# JHDH-8412_1247.net
KiCad netlist of a schematic drawn in Altium Designer
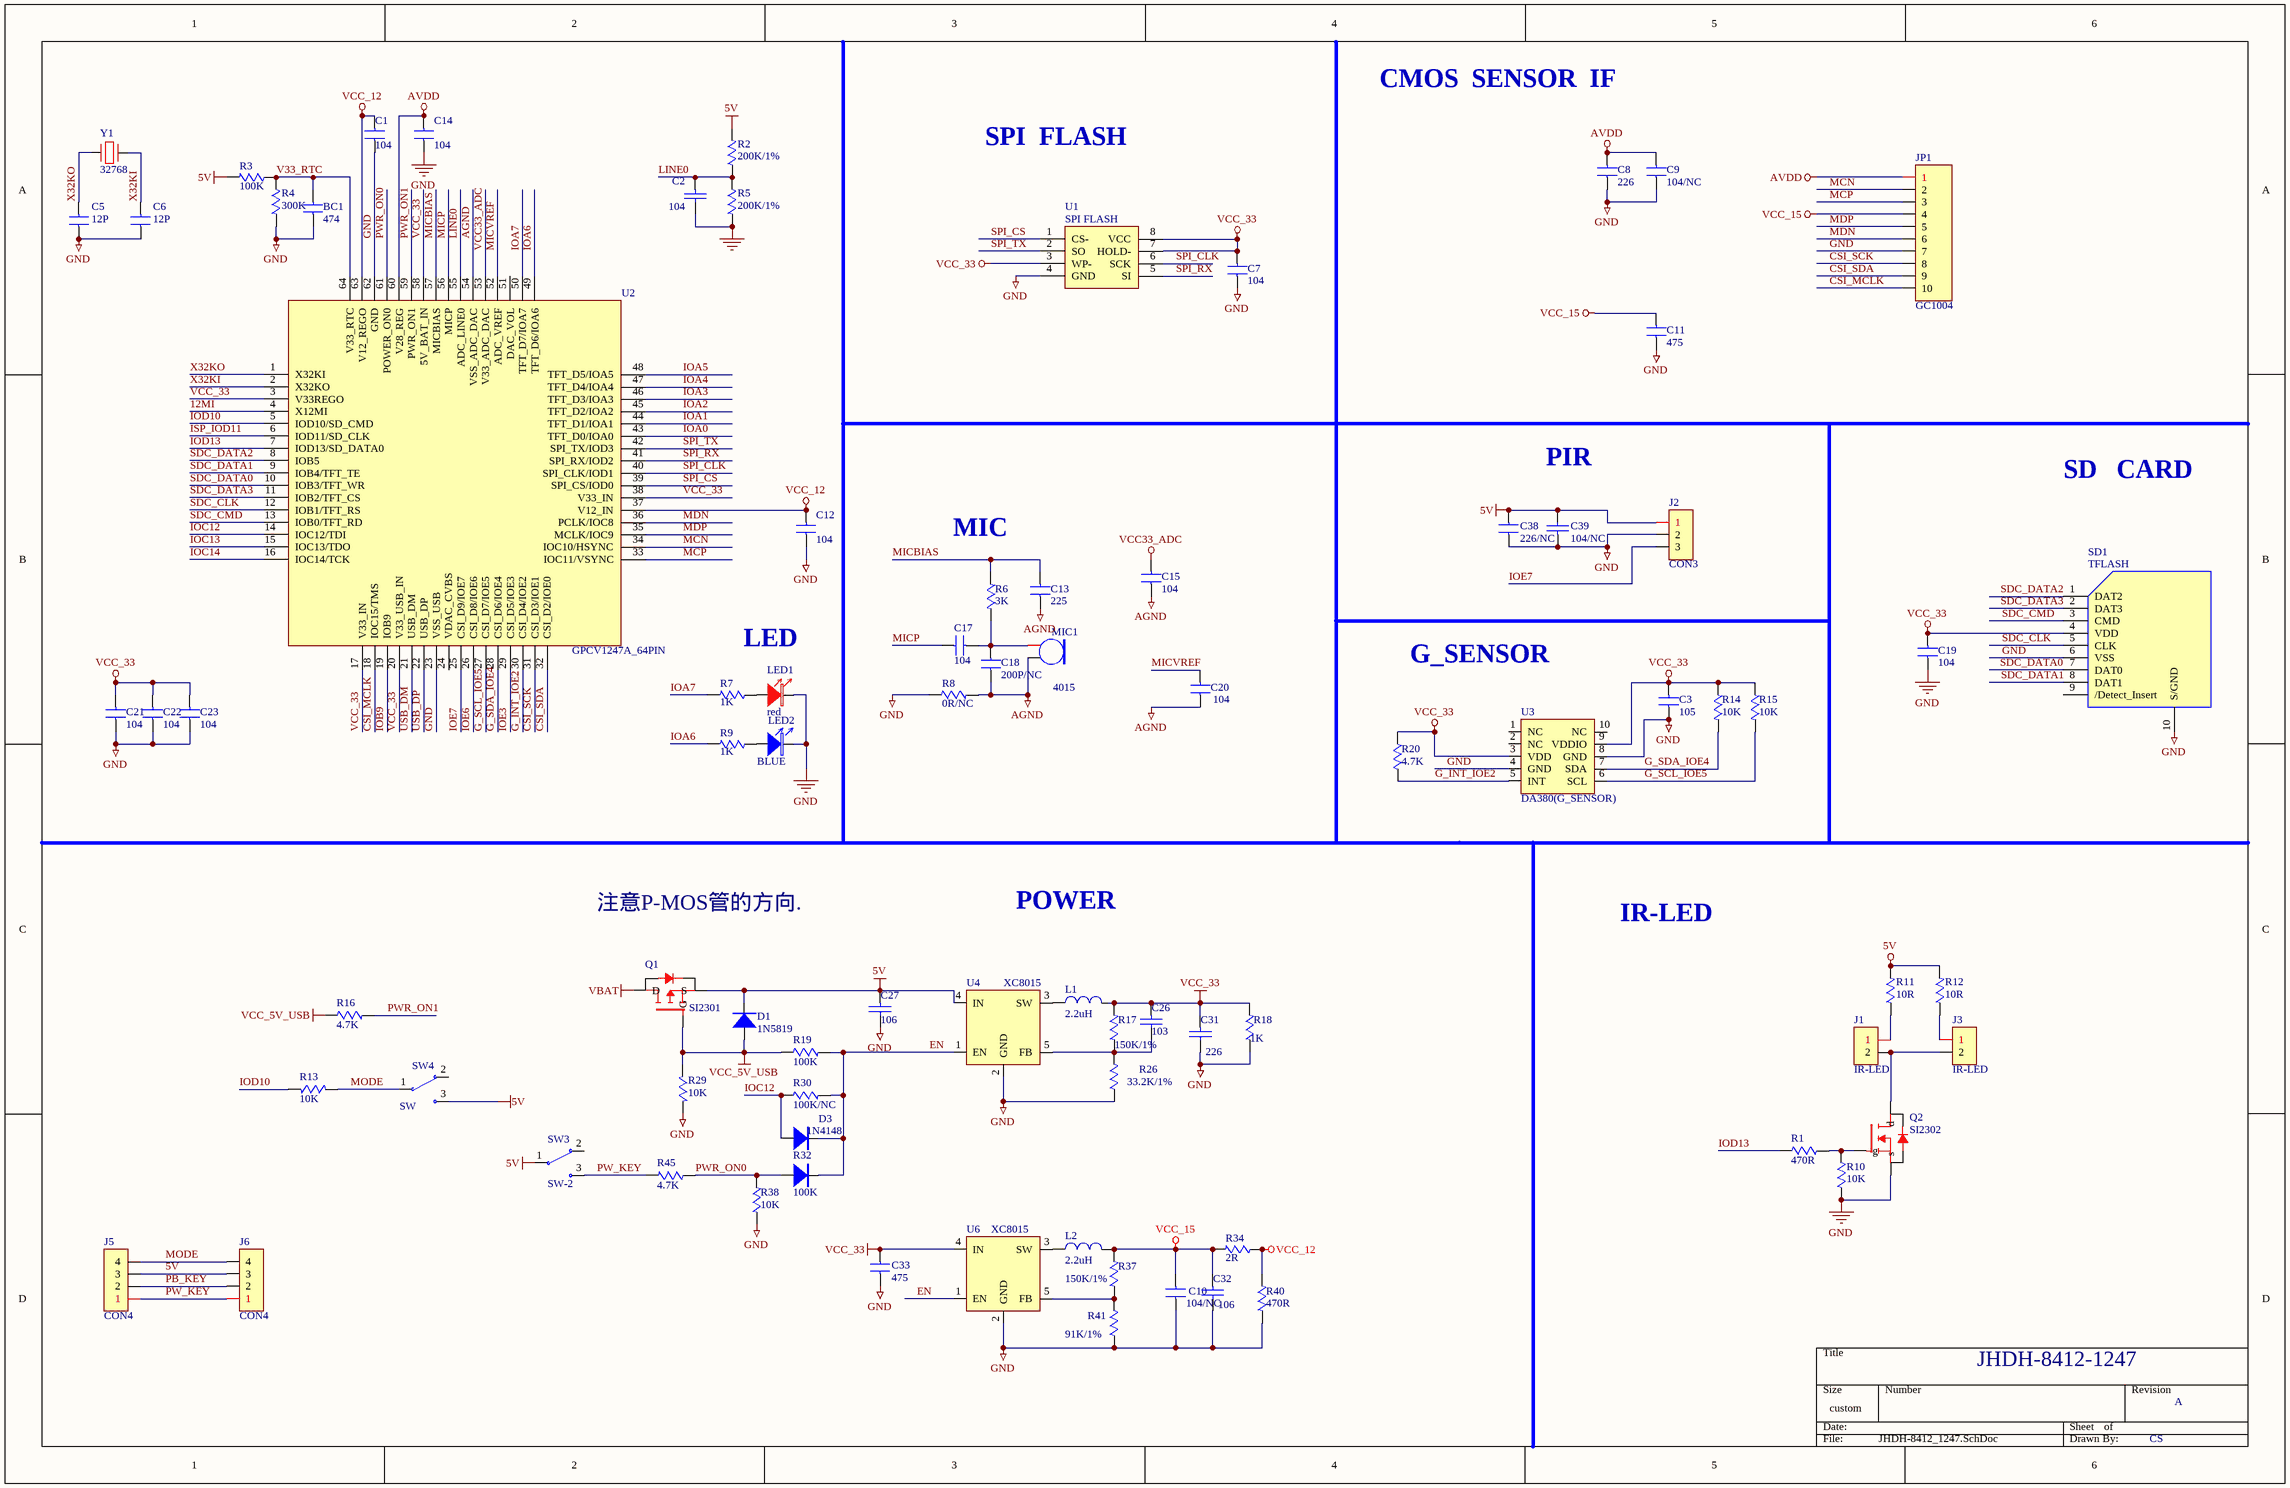
[diagram p0: JHDH-8412_1247.SchDoc]

(export (version "E")
  (design (tool "Eeschema 10.0.6"))
  (components
    (comp (ref "BC1")
      (value "474")
      (footprint "C0402")
      (description "Capacitor")
      (libsource (lib "*") (part "CAP"))
    )
    (comp (ref "C1")
      (value "104")
      (footprint "C0402")
      (description "Capacitor")
      (libsource (lib "*") (part "CAP"))
    )
    (comp (ref "C2")
      (value "104")
      (footprint "C0402")
      (description "贴片电容")
      (libsource (lib "") (part "CAP_1"))
    )
    (comp (ref "C3")
      (value "105")
      (footprint "C0402")
      (description "Capacitor")
      (libsource (lib "*") (part "CAP"))
    )
    (comp (ref "C5")
      (value "12P")
      (footprint "C0402")
      (description "Capacitor")
      (libsource (lib "*") (part "CAP"))
    )
    (comp (ref "C6")
      (value "12P")
      (footprint "C0402")
      (description "Capacitor")
      (libsource (lib "*") (part "CAP"))
    )
    (comp (ref "C7")
      (value "104")
      (footprint "C0402")
      (description "Capacitor")
      (libsource (lib "*") (part "CAP"))
    )
    (comp (ref "C8")
      (value "226")
      (footprint "C0805")
      (description "Capacitor")
      (libsource (lib "*") (part "CAP"))
    )
    (comp (ref "C9")
      (value "104/NC")
      (footprint "C0402")
      (description "Capacitor")
      (libsource (lib "*") (part "CAP"))
    )
    (comp (ref "C10")
      (value "104/NC")
      (footprint "C0402")
      (description "Capacitor")
      (libsource (lib "*") (part "CAP"))
    )
    (comp (ref "C11")
      (value "475")
      (footprint "C0603")
      (description "Capacitor")
      (libsource (lib "*") (part "CAP"))
    )
    (comp (ref "C12")
      (value "104")
      (footprint "C0402")
      (description "Capacitor")
      (libsource (lib "*") (part "CAP"))
    )
    (comp (ref "C13")
      (value "225")
      (footprint "C0402")
      (description "Capacitor")
      (libsource (lib "*") (part "CAP"))
    )
    (comp (ref "C14")
      (value "104")
      (footprint "C0402")
      (description "Capacitor")
      (libsource (lib "*") (part "CAP"))
    )
    (comp (ref "C15")
      (value "104")
      (footprint "C0402")
      (description "Capacitor")
      (libsource (lib "*") (part "CAP"))
    )
    (comp (ref "C17")
      (value "104")
      (footprint "C0402")
      (description "Capacitor")
      (libsource (lib "*") (part "CAP"))
    )
    (comp (ref "C18")
      (value "200P/NC")
      (footprint "C0402")
      (description "Capacitor")
      (libsource (lib "*") (part "CAP"))
    )
    (comp (ref "C19")
      (value "104")
      (footprint "C0603")
      (description "Capacitor")
      (libsource (lib "*") (part "CAP"))
    )
    (comp (ref "C20")
      (value "104")
      (footprint "C0402")
      (description "Capacitor")
      (libsource (lib "*") (part "CAP"))
    )
    (comp (ref "C21")
      (value "104")
      (footprint "C0402")
      (description "Capacitor")
      (libsource (lib "*") (part "CAP"))
    )
    (comp (ref "C22")
      (value "104")
      (footprint "C0402")
      (description "Capacitor")
      (libsource (lib "*") (part "CAP"))
    )
    (comp (ref "C23")
      (value "104")
      (footprint "C0402")
      (description "Capacitor")
      (libsource (lib "*") (part "CAP"))
    )
    (comp (ref "C26")
      (value "103")
      (footprint "C0402")
      (description "贴片电容")
      (libsource (lib "") (part "CAP_1"))
    )
    (comp (ref "C27")
      (value "106")
      (footprint "C0805")
      (description "贴片电容")
      (libsource (lib "") (part "CAP_1"))
    )
    (comp (ref "C31")
      (value "226")
      (footprint "C0805")
      (description "贴片电容")
      (libsource (lib "") (part "CAP_1"))
    )
    (comp (ref "C32")
      (value "106")
      (footprint "C0603")
      (description "贴片电容")
      (libsource (lib "") (part "CAP_1"))
    )
    (comp (ref "C33")
      (value "475")
      (footprint "C0603")
      (description "Capacitor")
      (libsource (lib "*") (part "CAP"))
    )
    (comp (ref "C38") (value "226/NC") (description "电容") (libsource (lib "SCH") (part "CAP")))
    (comp (ref "C39")
      (value "104/NC")
      (footprint "c0402")
      (description "Capacitor")
      (libsource (lib "") (part "CAP_1"))
    )
    (comp (ref "D1")
      (value "1N5819")
      (footprint "DO-214AC")
      (description "肖特基二极管")
      (libsource (lib "*") (part "1N5819"))
    )
    (comp (ref "D3")
      (value "1N4148")
      (footprint "D1206")
      (description "二极管")
      (libsource (lib "SCH") (part "DIODE"))
    )
    (comp (ref "J1")
      (value "IR-LED")
      (footprint "PIN-2/2.54")
      (description "Connector")
      (libsource (lib "SCH") (part "CON2"))
    )
    (comp (ref "J2")
      (value "CON3")
      (footprint "SIP3/2.0")
      (description "Connector")
      (libsource (lib "SCH") (part "CON3"))
    )
    (comp (ref "J3")
      (value "IR-LED")
      (footprint "PIN-2/2.54")
      (description "Connector")
      (libsource (lib "") (part "CON2_1"))
    )
    (comp (ref "J5")
      (value "CON4")
      (footprint "PIN-4/1.27")
      (description "Connector")
      (libsource (lib "") (part "CON4_1"))
    )
    (comp (ref "J6")
      (value "CON4")
      (footprint "PIN-4/1.27")
      (description "Connector")
      (libsource (lib "SCH") (part "CON4"))
    )
    (comp (ref "JP1")
      (value "GC1004")
      (footprint "10PIN-MIPI/0.5")
      (description "Connector")
      (libsource (lib "*") (part "CON10"))
    )
    (comp (ref "L1")
      (value "2.2uH")
      (footprint "L3015")
      (description "电感")
      (libsource (lib "*") (part "L-1"))
    )
    (comp (ref "L2")
      (value "2.2uH")
      (footprint "L3015")
      (description "电感")
      (libsource (lib "*") (part "L-1"))
    )
    (comp (ref "LED1")
      (value "red")
      (footprint "LED0603R")
      (description "LED/红色")
      (libsource (lib "SCH") (part "LED-R"))
    )
    (comp (ref "LED2")
      (value "BLUE")
      (footprint "LED0603B")
      (description "LED/blue")
      (libsource (lib "*") (part "LED-B"))
    )
    (comp (ref "MIC1")
      (value "4015")
      (footprint "MICE")
      (description "咪头")
      (libsource (lib "*") (part "MICROPHONE"))
    )
    (comp (ref "Q1")
      (value "SI2301")
      (footprint "SOT23")
      (description "场效应管/P")
      (libsource (lib "*") (part "MOSFETP"))
    )
    (comp (ref "Q2")
      (value "SI2302")
      (footprint "SOT23")
      (description "Mosfet/N")
      (libsource (lib "SCH") (part "MOSFETN"))
    )
    (comp (ref "R1")
      (value "470R")
      (footprint "R0402")
      (description "贴片电阻")
      (libsource (lib "SCH") (part "RES"))
    )
    (comp (ref "R2")
      (value "200K/1%")
      (footprint "R0402")
      (description "贴片电阻")
      (libsource (lib "*") (part "RES"))
    )
    (comp (ref "R3")
      (value "100K")
      (footprint "R0402")
      (description "贴片电阻")
      (libsource (lib "*") (part "RES"))
    )
    (comp (ref "R4")
      (value "300K")
      (footprint "R0402")
      (description "贴片电阻")
      (libsource (lib "*") (part "RES"))
    )
    (comp (ref "R5")
      (value "200K/1%")
      (footprint "R0402")
      (description "贴片电阻")
      (libsource (lib "*") (part "RES"))
    )
    (comp (ref "R6")
      (value "3K")
      (footprint "R0402")
      (description "Resistor")
      (libsource (lib "*") (part "RES"))
    )
    (comp (ref "R7")
      (value "1K")
      (footprint "R0402")
      (description "Resistor")
      (libsource (lib "*") (part "RES"))
    )
    (comp (ref "R8")
      (value "0R/NC")
      (footprint "R0402")
      (description "Resistor")
      (libsource (lib "*") (part "RES"))
    )
    (comp (ref "R9")
      (value "1K")
      (footprint "R0402")
      (description "Resistor")
      (libsource (lib "*") (part "RES"))
    )
    (comp (ref "R10")
      (value "10K")
      (footprint "R0402")
      (description "贴片电阻")
      (libsource (lib "SCH") (part "RES"))
    )
    (comp (ref "R11")
      (value "10R")
      (footprint "R1206")
      (description "贴片电阻")
      (libsource (lib "SCH") (part "RES"))
    )
    (comp (ref "R12")
      (value "10R")
      (footprint "R1206")
      (description "贴片电阻")
      (libsource (lib "SCH") (part "RES"))
    )
    (comp (ref "R13")
      (value "10K")
      (footprint "R0402")
      (description "贴片电阻")
      (libsource (lib "*") (part "RES"))
    )
    (comp (ref "R14")
      (value "10K")
      (footprint "R0402")
      (description "Resistor")
      (libsource (lib "*") (part "RES"))
    )
    (comp (ref "R15")
      (value "10K")
      (footprint "R0402")
      (description "Resistor")
      (libsource (lib "*") (part "RES"))
    )
    (comp (ref "R16")
      (value "4.7K")
      (footprint "R0402")
      (description "Resistor")
      (libsource (lib "*") (part "RES"))
    )
    (comp (ref "R17")
      (value "150K/1%")
      (footprint "R0402")
      (description "贴片电阻")
      (libsource (lib "*") (part "RES"))
    )
    (comp (ref "R18")
      (value "1K")
      (footprint "R0402")
      (description "贴片电阻")
      (libsource (lib "*") (part "RES"))
    )
    (comp (ref "R19")
      (value "100K")
      (footprint "R0402")
      (description "贴片电阻")
      (libsource (lib "SCH") (part "RES"))
    )
    (comp (ref "R20")
      (value "4.7K")
      (footprint "R0402")
      (description "Resistor")
      (libsource (lib "*") (part "RES"))
    )
    (comp (ref "R26")
      (value "33.2K/1%")
      (footprint "R0402")
      (description "贴片电阻")
      (libsource (lib "*") (part "RES"))
    )
    (comp (ref "R29")
      (value "10K")
      (footprint "R0402")
      (description "贴片电阻")
      (libsource (lib "*") (part "RES"))
    )
    (comp (ref "R30")
      (value "100K/NC")
      (footprint "R0402")
      (description "贴片电阻")
      (libsource (lib "SCH") (part "RES"))
    )
    (comp (ref "R32")
      (value "100K")
      (footprint "R0402")
      (description "二极管")
      (libsource (lib "SCH") (part "DIODE"))
    )
    (comp (ref "R34")
      (value "2R")
      (footprint "R0805")
      (description "Resistor")
      (libsource (lib "*") (part "RES"))
    )
    (comp (ref "R37")
      (value "150K/1%")
      (footprint "R0402")
      (description "贴片电阻")
      (libsource (lib "*") (part "RES"))
    )
    (comp (ref "R38")
      (value "10K")
      (footprint "R0402")
      (description "贴片电阻")
      (libsource (lib "*") (part "RES"))
    )
    (comp (ref "R40")
      (value "470R")
      (footprint "R0402")
      (description "Resistor")
      (libsource (lib "*") (part "RES"))
    )
    (comp (ref "R41")
      (value "91K/1%")
      (footprint "R0402")
      (description "贴片电阻")
      (libsource (lib "*") (part "RES"))
    )
    (comp (ref "R45")
      (value "4.7K")
      (footprint "R0402")
      (description "贴片电阻")
      (libsource (lib "SCH") (part "RES"))
    )
    (comp (ref "SD1")
      (value "TFLASH")
      (footprint "TFC-0002")
      (description "外卡卡座")
      (libsource (lib "*") (part "SD-MICRO"))
    )
    (comp (ref "SW3")
      (value "SW-2")
      (footprint "SW/MK-12C01")
      (description "Slide Switch")
      (libsource (lib "SCH") (part "SW-2"))
    )
    (comp (ref "SW4")
      (value "SW")
      (footprint "SW/MK-12C01")
      (description "Slide Switch")
      (libsource (lib "SCH") (part "SW-2"))
    )
    (comp (ref "U1") (value "SPI FLASH") (footprint "SOP8") (libsource (lib "*") (part "AT25010A")))
    (comp (ref "U2")
      (value "GPCV1247A_64PIN")
      (footprint "LQFP64-0.4")
      (libsource (lib "*") (part "GPCV12417A_64PIN"))
    )
    (comp (ref "U3")
      (value "DA380(G_SENSOR)")
      (footprint "QFN16-3*3-0.5-DA380")
      (description "G-Sensor")
      (libsource (lib "*") (part "DA380"))
    )
    (comp (ref "U4")
      (value "XC8015")
      (footprint "SOT23-5")
      (description "升压IC")
      (libsource (lib "*") (part "BL8021"))
    )
    (comp (ref "U6")
      (value "XC8015")
      (footprint "SOT23-5")
      (description "升压IC")
      (libsource (lib "*") (part "BL8021"))
    )
    (comp (ref "Y1")
      (value "32768")
      (footprint "XTAL-1.5X7")
      (description "Crystal")
      (libsource (lib "SCH") (part "CRYSTAL"))
    )
  )
  (nets
    (net (code "1") (name "/12MI") (class "Default")
      (node (ref "U2") (pin "4") (pinfunction "X12MI_4") (pintype "passive"))
    )
    (net (code "2") (name "/CSI_MCLK") (class "Default")
      (node (ref "JP1") (pin "10") (pinfunction "10_10") (pintype "passive"))
      (node (ref "U2") (pin "18") (pinfunction "IOC15/TMS_18") (pintype "passive"))
    )
    (net (code "3") (name "/CSI_SCK") (class "Default")
      (node (ref "JP1") (pin "8") (pinfunction "8_8") (pintype "passive"))
      (node (ref "U2") (pin "31") (pinfunction "CSI_D3/IOE1_31") (pintype "passive"))
    )
    (net (code "4") (name "/CSI_SDA") (class "Default")
      (node (ref "JP1") (pin "9") (pinfunction "9_9") (pintype "passive"))
      (node (ref "U2") (pin "32") (pinfunction "CSI_D2/IOE0_32") (pintype "passive"))
    )
    (net (code "5") (name "/EN") (class "Default")
      (node (ref "D3") (pin "2") (pinfunction "K_2") (pintype "passive"))
      (node (ref "R19") (pin "2") (pinfunction "2_2") (pintype "passive"))
      (node (ref "R30") (pin "2") (pinfunction "2_2") (pintype "passive"))
      (node (ref "R32") (pin "2") (pinfunction "K_2") (pintype "passive"))
      (node (ref "U4") (pin "1") (pinfunction "EN_1") (pintype "passive"))
      (node (ref "U6") (pin "1") (pinfunction "EN_1") (pintype "passive"))
    )
    (net (code "6") (name "/G_INT_IOE2") (class "Default")
      (node (ref "R20") (pin "2") (pinfunction "2_2") (pintype "passive"))
      (node (ref "U2") (pin "30") (pinfunction "CSI_D4/IOE2_30") (pintype "passive"))
      (node (ref "U3") (pin "5") (pinfunction "INT_5") (pintype "passive"))
    )
    (net (code "7") (name "/G_SCL_IOE5") (class "Default")
      (node (ref "R15") (pin "2") (pinfunction "2_2") (pintype "passive"))
      (node (ref "U2") (pin "27") (pinfunction "CSI_D7/IOE5_27") (pintype "passive"))
      (node (ref "U3") (pin "6") (pinfunction "SCL_6") (pintype "passive"))
    )
    (net (code "8") (name "/G_SDA_IOE4") (class "Default")
      (node (ref "R14") (pin "2") (pinfunction "2_2") (pintype "passive"))
      (node (ref "U2") (pin "28") (pinfunction "CSI_D6/IOE4_28") (pintype "passive"))
      (node (ref "U3") (pin "7") (pinfunction "SDA_7") (pintype "passive"))
    )
    (net (code "9") (name "/IOA0") (class "Default")
      (node (ref "U2") (pin "43") (pinfunction "TFT_D0/IOA0_43") (pintype "passive"))
    )
    (net (code "10") (name "/IOA1") (class "Default")
      (node (ref "U2") (pin "44") (pinfunction "TFT_D1/IOA1_44") (pintype "passive"))
    )
    (net (code "11") (name "/IOA2") (class "Default")
      (node (ref "U2") (pin "45") (pinfunction "TFT_D2/IOA2_45") (pintype "passive"))
    )
    (net (code "12") (name "/IOA3") (class "Default")
      (node (ref "U2") (pin "46") (pinfunction "TFT_D3/IOA3_46") (pintype "passive"))
    )
    (net (code "13") (name "/IOA4") (class "Default")
      (node (ref "U2") (pin "47") (pinfunction "TFT_D4/IOA4_47") (pintype "passive"))
    )
    (net (code "14") (name "/IOA5") (class "Default")
      (node (ref "U2") (pin "48") (pinfunction "TFT_D5/IOA5_48") (pintype "passive"))
    )
    (net (code "15") (name "/IOA6") (class "Default")
      (node (ref "R9") (pin "2") (pinfunction "2_2") (pintype "passive"))
      (node (ref "U2") (pin "49") (pinfunction "TFT_D6/IOA6_49") (pintype "passive"))
    )
    (net (code "16") (name "/IOA7") (class "Default")
      (node (ref "R7") (pin "2") (pinfunction "2_2") (pintype "passive"))
      (node (ref "U2") (pin "50") (pinfunction "TFT_D7/IOA7_50") (pintype "passive"))
    )
    (net (code "17") (name "/IOB9") (class "Default")
      (node (ref "U2") (pin "19") (pinfunction "IOB9_19") (pintype "passive"))
    )
    (net (code "18") (name "/IOC12") (class "Default")
      (node (ref "D3") (pin "1") (pinfunction "A_1") (pintype "passive"))
      (node (ref "R30") (pin "1") (pinfunction "1_1") (pintype "passive"))
      (node (ref "U2") (pin "14") (pinfunction "IOC12/TDI_14") (pintype "passive"))
    )
    (net (code "19") (name "/IOC13") (class "Default")
      (node (ref "U2") (pin "15") (pinfunction "IOC13/TDO_15") (pintype "passive"))
    )
    (net (code "20") (name "/IOC14") (class "Default")
      (node (ref "U2") (pin "16") (pinfunction "IOC14/TCK_16") (pintype "passive"))
    )
    (net (code "21") (name "/IOD10") (class "Default")
      (node (ref "R13") (pin "1") (pinfunction "1_1") (pintype "passive"))
      (node (ref "U2") (pin "5") (pinfunction "IOD10/SD_CMD_5") (pintype "passive"))
    )
    (net (code "22") (name "/IOD13") (class "Default")
      (node (ref "R1") (pin "1") (pinfunction "1_1") (pintype "passive"))
      (node (ref "U2") (pin "7") (pinfunction "IOD13/SD_DATA0_7") (pintype "passive"))
    )
    (net (code "23") (name "/IOE3") (class "Default")
      (node (ref "U2") (pin "29") (pinfunction "CSI_D5/IOE3_29") (pintype "passive"))
    )
    (net (code "24") (name "/IOE6") (class "Default")
      (node (ref "U2") (pin "26") (pinfunction "CSI_D8/IOE6_26") (pintype "passive"))
    )
    (net (code "25") (name "/IOE7") (class "Default")
      (node (ref "J2") (pin "3") (pinfunction "3_3") (pintype "passive"))
      (node (ref "U2") (pin "25") (pinfunction "CSI_D9/IOE7_25") (pintype "passive"))
    )
    (net (code "26") (name "/ISP_IOD11") (class "Default")
      (node (ref "U2") (pin "6") (pinfunction "IOD11/SD_CLK_6") (pintype "passive"))
    )
    (net (code "27") (name "/LINE0") (class "Default")
      (node (ref "C2") (pin "1") (pinfunction "1_1") (pintype "passive"))
      (node (ref "R2") (pin "1") (pinfunction "1_1") (pintype "passive"))
      (node (ref "R5") (pin "2") (pinfunction "2_2") (pintype "passive"))
      (node (ref "U2") (pin "55") (pinfunction "ADC_LINE0_55") (pintype "passive"))
    )
    (net (code "28") (name "/MCN") (class "Default")
      (node (ref "JP1") (pin "2") (pinfunction "2_2") (pintype "passive"))
      (node (ref "U2") (pin "34") (pinfunction "IOC10/HSYNC_34") (pintype "passive"))
    )
    (net (code "29") (name "/MCP") (class "Default")
      (node (ref "JP1") (pin "3") (pinfunction "3_3") (pintype "passive"))
      (node (ref "U2") (pin "33") (pinfunction "IOC11/VSYNC_33") (pintype "passive"))
    )
    (net (code "30") (name "/MDN") (class "Default")
      (node (ref "JP1") (pin "6") (pinfunction "6_6") (pintype "passive"))
      (node (ref "U2") (pin "36") (pinfunction "PCLK/IOC8_36") (pintype "passive"))
    )
    (net (code "31") (name "/MDP") (class "Default")
      (node (ref "JP1") (pin "5") (pinfunction "5_5") (pintype "passive"))
      (node (ref "U2") (pin "35") (pinfunction "MCLK/IOC9_35") (pintype "passive"))
    )
    (net (code "32") (name "/MICBIAS") (class "Default")
      (node (ref "C13") (pin "1") (pinfunction "1_1") (pintype "passive"))
      (node (ref "R6") (pin "1") (pinfunction "1_1") (pintype "passive"))
      (node (ref "U2") (pin "57") (pinfunction "MICBIAS_57") (pintype "passive"))
    )
    (net (code "33") (name "/MICP") (class "Default")
      (node (ref "C17") (pin "1") (pinfunction "1_1") (pintype "passive"))
      (node (ref "U2") (pin "56") (pinfunction "MICP_56") (pintype "passive"))
    )
    (net (code "34") (name "/MICVREF") (class "Default")
      (node (ref "C20") (pin "1") (pinfunction "1_1") (pintype "passive"))
      (node (ref "U2") (pin "52") (pinfunction "ADC_VREF_52") (pintype "passive"))
    )
    (net (code "35") (name "/MODE") (class "Default")
      (node (ref "J5") (pin "4") (pinfunction "4_4") (pintype "passive"))
      (node (ref "J6") (pin "4") (pinfunction "4_4") (pintype "passive"))
      (node (ref "R13") (pin "2") (pinfunction "2_2") (pintype "passive"))
      (node (ref "SW4") (pin "1") (pinfunction "1_1") (pintype "passive"))
    )
    (net (code "36") (name "/PB_KEY") (class "Default")
      (node (ref "J5") (pin "2") (pinfunction "2_2") (pintype "passive"))
      (node (ref "J6") (pin "2") (pinfunction "2_2") (pintype "passive"))
    )
    (net (code "37") (name "/PWR_ON0") (class "Default")
      (node (ref "R32") (pin "1") (pinfunction "A_1") (pintype "passive"))
      (node (ref "R38") (pin "2") (pinfunction "2_2") (pintype "passive"))
      (node (ref "R45") (pin "1") (pinfunction "1_1") (pintype "passive"))
      (node (ref "U2") (pin "61") (pinfunction "POWER_ON0_61") (pintype "passive"))
    )
    (net (code "38") (name "/PWR_ON1") (class "Default")
      (node (ref "R16") (pin "2") (pinfunction "2_2") (pintype "passive"))
      (node (ref "U2") (pin "59") (pinfunction "PWR_ON1_59") (pintype "passive"))
    )
    (net (code "39") (name "/PW_KEY") (class "Default")
      (node (ref "J5") (pin "1") (pinfunction "1_1") (pintype "passive"))
      (node (ref "J6") (pin "1") (pinfunction "1_1") (pintype "passive"))
      (node (ref "R45") (pin "2") (pinfunction "2_2") (pintype "passive"))
      (node (ref "SW3") (pin "3") (pinfunction "3_3") (pintype "passive"))
    )
    (net (code "40") (name "/SDC_CLK") (class "Default")
      (node (ref "SD1") (pin "5") (pinfunction "CLK_5") (pintype "power_in"))
      (node (ref "U2") (pin "12") (pinfunction "IOB1/TFT_RS_12") (pintype "passive"))
    )
    (net (code "41") (name "/SDC_CMD") (class "Default")
      (node (ref "SD1") (pin "3") (pinfunction "CMD_3") (pintype "power_in"))
      (node (ref "U2") (pin "13") (pinfunction "IOB0/TFT_RD_13") (pintype "passive"))
    )
    (net (code "42") (name "/SDC_DATA0") (class "Default")
      (node (ref "SD1") (pin "7") (pinfunction "DAT0_7") (pintype "power_in"))
      (node (ref "U2") (pin "10") (pinfunction "IOB3/TFT_WR_10") (pintype "passive"))
    )
    (net (code "43") (name "/SDC_DATA1") (class "Default")
      (node (ref "SD1") (pin "8") (pinfunction "DAT1_8") (pintype "power_in"))
      (node (ref "U2") (pin "9") (pinfunction "IOB4/TFT_TE_9") (pintype "passive"))
    )
    (net (code "44") (name "/SDC_DATA2") (class "Default")
      (node (ref "SD1") (pin "1") (pinfunction "DAT2_1") (pintype "power_in"))
      (node (ref "U2") (pin "8") (pinfunction "IOB5_8") (pintype "passive"))
    )
    (net (code "45") (name "/SDC_DATA3") (class "Default")
      (node (ref "SD1") (pin "2") (pinfunction "DAT3_2") (pintype "power_in"))
      (node (ref "U2") (pin "11") (pinfunction "IOB2/TFT_CS_11") (pintype "passive"))
    )
    (net (code "46") (name "/SPI_CLK") (class "Default")
      (node (ref "U1") (pin "6") (pinfunction "SCK_6") (pintype "passive"))
      (node (ref "U2") (pin "40") (pinfunction "SPI_CLK/IOD1_40") (pintype "passive"))
    )
    (net (code "47") (name "/SPI_CS") (class "Default")
      (node (ref "U1") (pin "1") (pinfunction "CS-_1") (pintype "passive"))
      (node (ref "U2") (pin "39") (pinfunction "SPI_CS/IOD0_39") (pintype "passive"))
    )
    (net (code "48") (name "/SPI_RX") (class "Default")
      (node (ref "U1") (pin "5") (pinfunction "SI_5") (pintype "passive"))
      (node (ref "U2") (pin "41") (pinfunction "SPI_RX/IOD2_41") (pintype "passive"))
    )
    (net (code "49") (name "/SPI_TX") (class "Default")
      (node (ref "U1") (pin "2") (pinfunction "SO_2") (pintype "passive"))
      (node (ref "U2") (pin "42") (pinfunction "SPI_TX/IOD3_42") (pintype "passive"))
    )
    (net (code "50") (name "/USB_DM") (class "Default")
      (node (ref "U2") (pin "21") (pinfunction "USB_DM_21") (pintype "passive"))
    )
    (net (code "51") (name "/USB_DP") (class "Default")
      (node (ref "U2") (pin "22") (pinfunction "USB_DP_22") (pintype "passive"))
    )
    (net (code "52") (name "/V33_RTC") (class "Default")
      (node (ref "BC1") (pin "1") (pinfunction "1_1") (pintype "passive"))
      (node (ref "R3") (pin "1") (pinfunction "1_1") (pintype "passive"))
      (node (ref "R4") (pin "2") (pinfunction "2_2") (pintype "passive"))
      (node (ref "U2") (pin "64") (pinfunction "V33_RTC_64") (pintype "passive"))
    )
    (net (code "53") (name "/X32KI") (class "Default")
      (node (ref "C6") (pin "1") (pinfunction "1_1") (pintype "passive"))
      (node (ref "U2") (pin "2") (pinfunction "X32KO_2") (pintype "passive"))
      (node (ref "Y1") (pin "2") (pinfunction "2_2") (pintype "passive"))
    )
    (net (code "54") (name "/X32KO") (class "Default")
      (node (ref "C5") (pin "1") (pinfunction "1_1") (pintype "passive"))
      (node (ref "U2") (pin "1") (pinfunction "X32KI_1") (pintype "passive"))
      (node (ref "Y1") (pin "1") (pinfunction "1_1") (pintype "passive"))
    )
    (net (code "55") (name "5V") (class "Default")
      (node (ref "C27") (pin "1") (pinfunction "1_1") (pintype "passive"))
      (node (ref "C38") (pin "1") (pinfunction "1_1") (pintype "passive"))
      (node (ref "C39") (pin "2") (pinfunction "2_2") (pintype "passive"))
      (node (ref "D1") (pin "2") (pinfunction "K_2") (pintype "passive"))
      (node (ref "J2") (pin "1") (pinfunction "1_1") (pintype "passive"))
      (node (ref "J5") (pin "3") (pinfunction "3_3") (pintype "passive"))
      (node (ref "J6") (pin "3") (pinfunction "3_3") (pintype "passive"))
      (node (ref "Q1") (pin "2") (pinfunction "S_2") (pintype "passive"))
      (node (ref "R11") (pin "2") (pinfunction "2_2") (pintype "passive"))
      (node (ref "R12") (pin "2") (pinfunction "2_2") (pintype "passive"))
      (node (ref "R2") (pin "2") (pinfunction "2_2") (pintype "passive"))
      (node (ref "R3") (pin "2") (pinfunction "2_2") (pintype "passive"))
      (node (ref "SW3") (pin "1") (pinfunction "1_1") (pintype "passive"))
      (node (ref "SW4") (pin "3") (pinfunction "3_3") (pintype "passive"))
      (node (ref "U4") (pin "4") (pinfunction "IN_4") (pintype "passive"))
    )
    (net (code "56") (name "AGND") (class "Default")
      (node (ref "C13") (pin "2") (pinfunction "2_2") (pintype "passive"))
      (node (ref "C15") (pin "2") (pinfunction "2_2") (pintype "passive"))
      (node (ref "C18") (pin "1") (pinfunction "1_1") (pintype "passive"))
      (node (ref "C20") (pin "2") (pinfunction "2_2") (pintype "passive"))
      (node (ref "MIC1") (pin "2") (pinfunction "2_2") (pintype "passive"))
      (node (ref "R8") (pin "2") (pinfunction "2_2") (pintype "passive"))
      (node (ref "U2") (pin "54") (pinfunction "VSS_ADC_DAC_54") (pintype "passive"))
    )
    (net (code "57") (name "AVDD") (class "Default")
      (node (ref "C14") (pin "1") (pinfunction "1_1") (pintype "passive"))
      (node (ref "C8") (pin "1") (pinfunction "1_1") (pintype "passive"))
      (node (ref "C9") (pin "1") (pinfunction "1_1") (pintype "passive"))
      (node (ref "JP1") (pin "1") (pinfunction "1_1") (pintype "passive"))
      (node (ref "U2") (pin "60") (pinfunction "V28_REG_60") (pintype "passive"))
    )
    (net (code "58") (name "GND") (class "Default")
      (node (ref "BC1") (pin "2") (pinfunction "2_2") (pintype "passive"))
      (node (ref "C1") (pin "2") (pinfunction "2_2") (pintype "passive"))
      (node (ref "C10") (pin "2") (pinfunction "2_2") (pintype "passive"))
      (node (ref "C11") (pin "2") (pinfunction "2_2") (pintype "passive"))
      (node (ref "C12") (pin "2") (pinfunction "2_2") (pintype "passive"))
      (node (ref "C14") (pin "2") (pinfunction "2_2") (pintype "passive"))
      (node (ref "C19") (pin "2") (pinfunction "2_2") (pintype "passive"))
      (node (ref "C2") (pin "2") (pinfunction "2_2") (pintype "passive"))
      (node (ref "C21") (pin "2") (pinfunction "2_2") (pintype "passive"))
      (node (ref "C22") (pin "2") (pinfunction "2_2") (pintype "passive"))
      (node (ref "C23") (pin "2") (pinfunction "2_2") (pintype "passive"))
      (node (ref "C27") (pin "2") (pinfunction "2_2") (pintype "passive"))
      (node (ref "C3") (pin "2") (pinfunction "2_2") (pintype "passive"))
      (node (ref "C31") (pin "2") (pinfunction "2_2") (pintype "passive"))
      (node (ref "C32") (pin "2") (pinfunction "2_2") (pintype "passive"))
      (node (ref "C33") (pin "1") (pinfunction "1_1") (pintype "passive"))
      (node (ref "C38") (pin "2") (pinfunction "2_2") (pintype "passive"))
      (node (ref "C39") (pin "1") (pinfunction "1_1") (pintype "passive"))
      (node (ref "C5") (pin "2") (pinfunction "2_2") (pintype "passive"))
      (node (ref "C6") (pin "2") (pinfunction "2_2") (pintype "passive"))
      (node (ref "C7") (pin "2") (pinfunction "2_2") (pintype "passive"))
      (node (ref "C8") (pin "2") (pinfunction "2_2") (pintype "passive"))
      (node (ref "C9") (pin "2") (pinfunction "2_2") (pintype "passive"))
      (node (ref "J2") (pin "2") (pinfunction "2_2") (pintype "passive"))
      (node (ref "JP1") (pin "7") (pinfunction "7_7") (pintype "passive"))
      (node (ref "LED1") (pin "2") (pinfunction "K_2") (pintype "passive"))
      (node (ref "LED2") (pin "2") (pinfunction "K_2") (pintype "passive"))
      (node (ref "Q2") (pin "2") (pinfunction "s_2") (pintype "passive"))
      (node (ref "R10") (pin "1") (pinfunction "1_1") (pintype "passive"))
      (node (ref "R18") (pin "1") (pinfunction "1_1") (pintype "passive"))
      (node (ref "R26") (pin "1") (pinfunction "1_1") (pintype "passive"))
      (node (ref "R29") (pin "2") (pinfunction "2_2") (pintype "passive"))
      (node (ref "R38") (pin "1") (pinfunction "1_1") (pintype "passive"))
      (node (ref "R4") (pin "1") (pinfunction "1_1") (pintype "passive"))
      (node (ref "R40") (pin "1") (pinfunction "1_1") (pintype "passive"))
      (node (ref "R41") (pin "1") (pinfunction "1_1") (pintype "passive"))
      (node (ref "R5") (pin "1") (pinfunction "1_1") (pintype "passive"))
      (node (ref "R8") (pin "1") (pinfunction "1_1") (pintype "passive"))
      (node (ref "SD1") (pin "10") (pinfunction "S/GND_10") (pintype "power_in"))
      (node (ref "SD1") (pin "6") (pinfunction "VSS_6") (pintype "power_in"))
      (node (ref "U1") (pin "4") (pinfunction "GND_4") (pintype "passive"))
      (node (ref "U2") (pin "23") (pinfunction "VSS_USB_23") (pintype "passive"))
      (node (ref "U2") (pin "62") (pinfunction "GND_62") (pintype "passive"))
      (node (ref "U3") (pin "4") (pinfunction "GND_4") (pintype "passive"))
      (node (ref "U3") (pin "8") (pinfunction "GND_8") (pintype "passive"))
      (node (ref "U4") (pin "2") (pinfunction "GND_2") (pintype "passive"))
      (node (ref "U6") (pin "2") (pinfunction "GND_2") (pintype "passive"))
    )
    (net (code "59") (name "Net-(C17-Pad2)") (class "Default")
      (node (ref "C17") (pin "2") (pinfunction "2_2") (pintype "passive"))
      (node (ref "C18") (pin "2") (pinfunction "2_2") (pintype "passive"))
      (node (ref "MIC1") (pin "1") (pinfunction "1_1") (pintype "passive"))
      (node (ref "R6") (pin "2") (pinfunction "2_2") (pintype "passive"))
    )
    (net (code "60") (name "Net-(J1-Pad1)") (class "Default")
      (node (ref "J1") (pin "1") (pinfunction "1_1") (pintype "passive"))
      (node (ref "R11") (pin "1") (pinfunction "1_1") (pintype "passive"))
    )
    (net (code "61") (name "Net-(J3-Pad1)") (class "Default")
      (node (ref "J3") (pin "1") (pinfunction "1_1") (pintype "passive"))
      (node (ref "R12") (pin "1") (pinfunction "1_1") (pintype "passive"))
    )
    (net (code "62") (name "Net-(LED1-A)") (class "Default")
      (node (ref "LED1") (pin "1") (pinfunction "A_1") (pintype "passive"))
      (node (ref "R7") (pin "1") (pinfunction "1_1") (pintype "passive"))
    )
    (net (code "63") (name "Net-(LED2-A)") (class "Default")
      (node (ref "LED2") (pin "1") (pinfunction "A_1") (pintype "passive"))
      (node (ref "R9") (pin "1") (pinfunction "1_1") (pintype "passive"))
    )
    (net (code "64") (name "Net-(Q2-d)") (class "Default")
      (node (ref "J1") (pin "2") (pinfunction "2_2") (pintype "passive"))
      (node (ref "J3") (pin "2") (pinfunction "2_2") (pintype "passive"))
      (node (ref "Q2") (pin "3") (pinfunction "d_3") (pintype "passive"))
    )
    (net (code "65") (name "Net-(Q2-g)") (class "Default")
      (node (ref "Q2") (pin "1") (pinfunction "g_1") (pintype "passive"))
      (node (ref "R1") (pin "2") (pinfunction "2_2") (pintype "passive"))
      (node (ref "R10") (pin "2") (pinfunction "2_2") (pintype "passive"))
    )
    (net (code "66") (name "Net-(U4-FB)") (class "Default")
      (node (ref "C26") (pin "2") (pinfunction "2_2") (pintype "passive"))
      (node (ref "R17") (pin "1") (pinfunction "1_1") (pintype "passive"))
      (node (ref "R26") (pin "2") (pinfunction "2_2") (pintype "passive"))
      (node (ref "U4") (pin "5") (pinfunction "FB_5") (pintype "passive"))
    )
    (net (code "67") (name "Net-(U4-SW)") (class "Default")
      (node (ref "L1") (pin "1") (pinfunction "1_1") (pintype "passive"))
      (node (ref "U4") (pin "3") (pinfunction "SW_3") (pintype "passive"))
    )
    (net (code "68") (name "Net-(U6-FB)") (class "Default")
      (node (ref "R37") (pin "1") (pinfunction "1_1") (pintype "passive"))
      (node (ref "R41") (pin "2") (pinfunction "2_2") (pintype "passive"))
      (node (ref "U6") (pin "5") (pinfunction "FB_5") (pintype "passive"))
    )
    (net (code "69") (name "Net-(U6-SW)") (class "Default")
      (node (ref "L2") (pin "1") (pinfunction "1_1") (pintype "passive"))
      (node (ref "U6") (pin "3") (pinfunction "SW_3") (pintype "passive"))
    )
    (net (code "70") (name "VBAT") (class "Default")
      (node (ref "Q1") (pin "3") (pinfunction "D_3") (pintype "passive"))
    )
    (net (code "71") (name "VCC33_ADC") (class "Default")
      (node (ref "C15") (pin "1") (pinfunction "1_1") (pintype "passive"))
      (node (ref "U2") (pin "53") (pinfunction "V33_ADC_DAC_53") (pintype "passive"))
    )
    (net (code "72") (name "VCC_5V_USB") (class "Default")
      (node (ref "D1") (pin "1") (pinfunction "A_1") (pintype "passive"))
      (node (ref "Q1") (pin "1") (pinfunction "G_1") (pintype "passive"))
      (node (ref "R16") (pin "1") (pinfunction "1_1") (pintype "passive"))
      (node (ref "R19") (pin "1") (pinfunction "1_1") (pintype "passive"))
      (node (ref "R29") (pin "1") (pinfunction "1_1") (pintype "passive"))
    )
    (net (code "73") (name "VCC_12") (class "Default")
      (node (ref "C1") (pin "1") (pinfunction "1_1") (pintype "passive"))
      (node (ref "C12") (pin "1") (pinfunction "1_1") (pintype "passive"))
      (node (ref "R34") (pin "1") (pinfunction "1_1") (pintype "passive"))
      (node (ref "R40") (pin "2") (pinfunction "2_2") (pintype "passive"))
      (node (ref "U2") (pin "37") (pinfunction "V12_IN_37") (pintype "passive"))
      (node (ref "U2") (pin "63") (pinfunction "V12_REGO_63") (pintype "passive"))
    )
    (net (code "74") (name "VCC_15") (class "Default")
      (node (ref "C10") (pin "1") (pinfunction "1_1") (pintype "passive"))
      (node (ref "C11") (pin "1") (pinfunction "1_1") (pintype "passive"))
      (node (ref "C32") (pin "1") (pinfunction "1_1") (pintype "passive"))
      (node (ref "JP1") (pin "4") (pinfunction "4_4") (pintype "passive"))
      (node (ref "L2") (pin "2") (pinfunction "2_2") (pintype "passive"))
      (node (ref "R34") (pin "2") (pinfunction "2_2") (pintype "passive"))
      (node (ref "R37") (pin "2") (pinfunction "2_2") (pintype "passive"))
    )
    (net (code "75") (name "VCC_33") (class "Default")
      (node (ref "C19") (pin "1") (pinfunction "1_1") (pintype "passive"))
      (node (ref "C21") (pin "1") (pinfunction "1_1") (pintype "passive"))
      (node (ref "C22") (pin "1") (pinfunction "1_1") (pintype "passive"))
      (node (ref "C23") (pin "1") (pinfunction "1_1") (pintype "passive"))
      (node (ref "C26") (pin "1") (pinfunction "1_1") (pintype "passive"))
      (node (ref "C3") (pin "1") (pinfunction "1_1") (pintype "passive"))
      (node (ref "C31") (pin "1") (pinfunction "1_1") (pintype "passive"))
      (node (ref "C33") (pin "2") (pinfunction "2_2") (pintype "passive"))
      (node (ref "C7") (pin "1") (pinfunction "1_1") (pintype "passive"))
      (node (ref "L1") (pin "2") (pinfunction "2_2") (pintype "passive"))
      (node (ref "R14") (pin "1") (pinfunction "1_1") (pintype "passive"))
      (node (ref "R15") (pin "1") (pinfunction "1_1") (pintype "passive"))
      (node (ref "R17") (pin "2") (pinfunction "2_2") (pintype "passive"))
      (node (ref "R18") (pin "2") (pinfunction "2_2") (pintype "passive"))
      (node (ref "R20") (pin "1") (pinfunction "1_1") (pintype "passive"))
      (node (ref "SD1") (pin "4") (pinfunction "VDD_4") (pintype "power_in"))
      (node (ref "U1") (pin "3") (pinfunction "WP-_3") (pintype "passive"))
      (node (ref "U1") (pin "7") (pinfunction "HOLD-_7") (pintype "passive"))
      (node (ref "U1") (pin "8") (pinfunction "VCC_8") (pintype "passive"))
      (node (ref "U2") (pin "17") (pinfunction "V33_IN_17") (pintype "passive"))
      (node (ref "U2") (pin "20") (pinfunction "V33_USB_IN_20") (pintype "passive"))
      (node (ref "U2") (pin "3") (pinfunction "V33REGO_3") (pintype "passive"))
      (node (ref "U2") (pin "38") (pinfunction "V33_IN_38") (pintype "passive"))
      (node (ref "U2") (pin "58") (pinfunction "5V_BAT_IN_58") (pintype "passive"))
      (node (ref "U3") (pin "3") (pinfunction "VDD_3") (pintype "passive"))
      (node (ref "U3") (pin "9") (pinfunction "VDDIO_9") (pintype "passive"))
      (node (ref "U6") (pin "4") (pinfunction "IN_4") (pintype "passive"))
    )
    (net (code "76") (name "unconnected-(SD1-{slash}Detect_Insert-Pad9)") (class "Default")
      (node (ref "SD1") (pin "9") (pinfunction "/Detect_Insert_9") (pintype "power_in"))
    )
    (net (code "77") (name "unconnected-(SW3-Pad2)") (class "Default")
      (node (ref "SW3") (pin "2") (pinfunction "2_2") (pintype "passive"))
    )
    (net (code "78") (name "unconnected-(SW4-Pad2)") (class "Default")
      (node (ref "SW4") (pin "2") (pinfunction "2_2") (pintype "passive"))
    )
    (net (code "79") (name "unconnected-(U2-DAC_VOL-Pad51)") (class "Default")
      (node (ref "U2") (pin "51") (pinfunction "DAC_VOL_51") (pintype "passive"))
    )
    (net (code "80") (name "unconnected-(U2-VDAC_CVBS-Pad24)") (class "Default")
      (node (ref "U2") (pin "24") (pinfunction "VDAC_CVBS_24") (pintype "passive"))
    )
    (net (code "81") (name "unconnected-(U3-NC-Pad1)") (class "Default")
      (node (ref "U3") (pin "1") (pinfunction "NC_1") (pintype "passive"))
    )
    (net (code "82") (name "unconnected-(U3-NC-Pad2)") (class "Default")
      (node (ref "U3") (pin "2") (pinfunction "NC_2") (pintype "passive"))
    )
    (net (code "83") (name "unconnected-(U3-NC-Pad10)") (class "Default")
      (node (ref "U3") (pin "10") (pinfunction "NC_10") (pintype "passive"))
    )
  )
)
